# KinetisDIP.net
KiCad netlist of a schematic drawn in Altium Designer
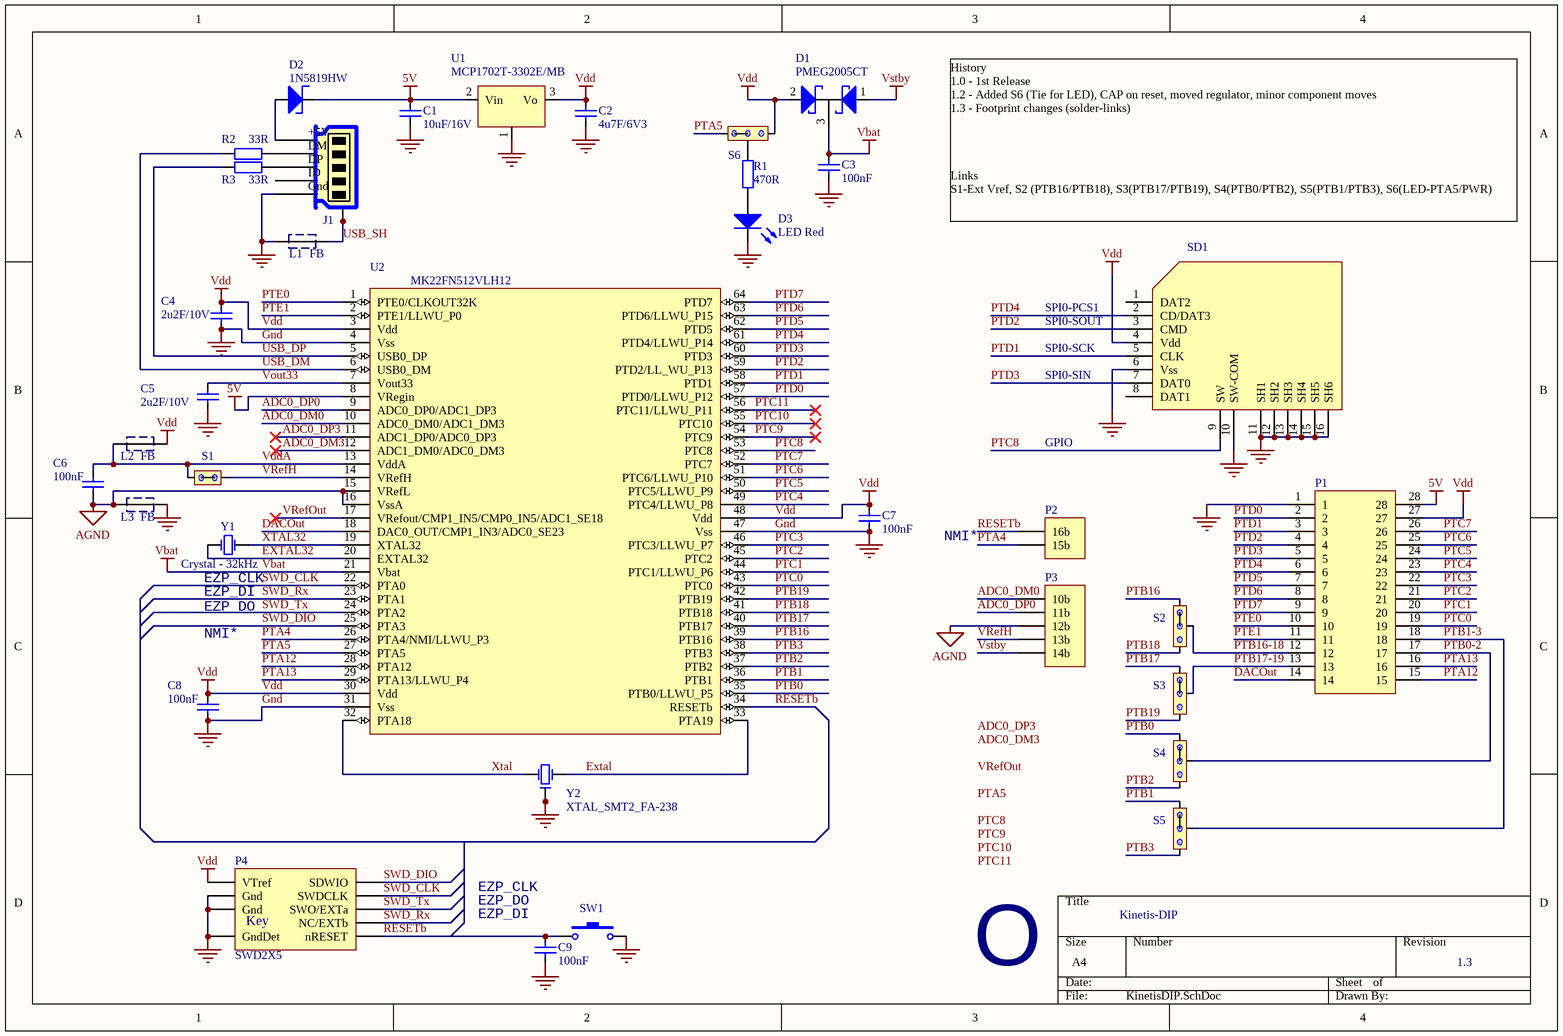
[diagram p0: KinetisDIP.SchDoc]

(export (version "E")
  (design (tool "Eeschema 10.0.6"))
  (components
    (comp (ref "C1")
      (value "10uF/16V")
      (footprint "CCNP2012-0805")
      (description "Capacitor SMT 0805")
      (fields
        (field (name "MANUFACTURER") "Generic Components")
        (field (name "PUBLISHER") "Altium Hobart Technology Centre")
      )
      (libsource (lib "MyLibrary") (part "Cap_CCNP_0805"))
    )
    (comp (ref "C2")
      (value "4u7F/6V3")
      (footprint "CCNP1608-0603")
      (description "Capacitor SMT 0603")
      (fields
        (field (name "MANUFACTURER") "Generic Components")
        (field (name "PUBLISHER") "Altium Hobart Technology Centre")
      )
      (libsource (lib "MyLibrary") (part "Cap_CCNP_0603"))
    )
    (comp (ref "C3")
      (value "100nF")
      (footprint "CCNP1608-0603")
      (description "Capacitor SMT 0603")
      (fields
        (field (name "MANUFACTURER") "Generic Components")
        (field (name "PUBLISHER") "Altium Hobart Technology Centre")
      )
      (libsource (lib "MyLibrary") (part "Cap_CCNP_0603"))
    )
    (comp (ref "C4")
      (value "2u2F/10V")
      (footprint "CCNP1608-0603")
      (description "Capacitor")
      (fields
        (field (name "MANUFACTURER") "Generic Components")
        (field (name "PUBLISHER") "Altium Hobart Technology Centre")
      )
      (libsource (lib "MyLibrary") (part "Cap"))
    )
    (comp (ref "C5")
      (value "2u2F/10V")
      (footprint "CCNP1608-0603")
      (description "Capacitor")
      (fields
        (field (name "MANUFACTURER") "Generic Components")
        (field (name "PUBLISHER") "Altium Hobart Technology Centre")
      )
      (libsource (lib "MyLibrary") (part "Cap"))
    )
    (comp (ref "C6")
      (value "100nF")
      (footprint "CCNP1608-0603")
      (description "Capacitor SMT 0603")
      (fields
        (field (name "MANUFACTURER") "Generic Components")
        (field (name "PUBLISHER") "Altium Hobart Technology Centre")
      )
      (libsource (lib "MyLibrary") (part "Cap_CCNP_0603"))
    )
    (comp (ref "C7")
      (value "100nF")
      (footprint "CCNP1608-0603")
      (description "Capacitor SMT 0603")
      (fields
        (field (name "MANUFACTURER") "Generic Components")
        (field (name "PUBLISHER") "Altium Hobart Technology Centre")
      )
      (libsource (lib "MyLibrary") (part "Cap_CCNP_0603"))
    )
    (comp (ref "C8")
      (value "100nF")
      (footprint "CCNP1608-0603")
      (description "Capacitor SMT 0603")
      (fields
        (field (name "MANUFACTURER") "Generic Components")
        (field (name "PUBLISHER") "Altium Hobart Technology Centre")
      )
      (libsource (lib "MyLibrary") (part "Cap_CCNP_0603"))
    )
    (comp (ref "C9")
      (value "100nF")
      (footprint "CCNP1608-0603")
      (description "Capacitor SMT 0603")
      (fields
        (field (name "MANUFACTURER") "Generic Components")
        (field (name "PUBLISHER") "Altium Hobart Technology Centre")
      )
      (libsource (lib "MyLibrary") (part "Cap_CCNP_0603"))
    )
    (comp (ref "D1")
      (value "PMEG2005CT")
      (footprint "SOT23")
      (description "Dual Schottky Diode (SMT)")
      (libsource (lib "MyLibrary") (part "PMEG2005CT"))
    )
    (comp (ref "D2")
      (value "1N5819HW")
      (footprint "SOD-123")
      (description "SCHOTTKY, 1A, 40V, SOD-123")
      (fields
        (field (name "MANUFACTURER") "Generic Components")
        (field (name "PUBLISHER") "Altium Hobart Technology Centre")
      )
      (libsource (lib "MySchLib") (part "1N5819HW"))
    )
    (comp (ref "D3")
      (value "LED Red")
      (footprint "LED1608-0603-RED")
      (description "LED 0603 Red")
      (fields (field (name "MANUFACTURER") "Generic Components") (field (name "PUBLISHER") "Altium Limited"))
      (libsource (lib "MyLibrary") (part "LED-0603-Red"))
    )
    (comp (ref "J1")
      (value "USB_MICRO_B_CONNECTOR")
      (footprint "MOLEX - 47346-0001")
      (description "USB Micro-B Connector")
      (libsource (lib "MySchLib") (part "USB_MICRO_B_CONNECTOR"))
    )
    (comp (ref "L1")
      (value "FB")
      (footprint "CR1608-0603")
      (description "Ferrite Bead (0603)")
      (libsource (lib "MyLibrary") (part "Ferrite Bead_0603"))
    )
    (comp (ref "L2")
      (value "FB")
      (footprint "CR1608-0603")
      (description "Ferrite Bead (0603)")
      (libsource (lib "MyLibrary") (part "Ferrite Bead_0603"))
    )
    (comp (ref "L3")
      (value "FB")
      (footprint "CR1608-0603")
      (description "Ferrite Bead (0603)")
      (libsource (lib "MyLibrary") (part "Ferrite Bead_0603"))
    )
    (comp (ref "Logo")
      (value "OSHW Logo")
      (footprint "OSHW")
      (libsource (lib "MyLibrary") (part "OSHW Logo"))
    )
    (comp (ref "P1")
      (value "WDIP-28-0.6")
      (footprint "WDIP-28-0.6")
      (description "Wide SIP package (0.6\")")
      (libsource (lib "MyLibrary") (part "WDIP-28-0.6"))
    )
    (comp (ref "P2")
      (value "Header 2")
      (footprint "HDR1X2")
      (description "Header, 2-Pin")
      (fields (field (name "PUBLISHER") "Altium Limited"))
      (libsource (lib "Miscellaneous Connectors") (part "Header 2"))
    )
    (comp (ref "P3")
      (value "Header 5")
      (footprint "HDR1X5")
      (description "Header, 5-Pin")
      (fields (field (name "PUBLISHER") "Altium Limited"))
      (libsource (lib "Miscellaneous Connectors") (part "Header 5"))
    )
    (comp (ref "P4")
      (value "SWD2X5")
      (footprint "SWD-2x5")
      (description "SWD Connector 2x5-Pin")
      (fields (field (name "PUBLISHER") "Altium Limited"))
      (libsource (lib "MySchLib") (part "SWD2X5"))
    )
    (comp (ref "R1")
      (value "470R")
      (footprint "CR1608-0603")
      (description "Resistor SMT")
      (fields
        (field (name "MANUFACTURER") "Generic Components")
        (field (name "PUBLISHER") "Altium Hobart Technology Centre")
      )
      (libsource (lib "MyLibrary") (part "Res"))
    )
    (comp (ref "R2")
      (value "33R")
      (footprint "CR1608-0603")
      (description "Resistor")
      (fields
        (field (name "MANUFACTURER") "Generic Components")
        (field (name "PUBLISHER") "Altium Hobart Technology Centre")
      )
      (libsource (lib "") (part "Res_1"))
    )
    (comp (ref "R3")
      (value "33R")
      (footprint "CR1608-0603")
      (description "Resistor")
      (fields
        (field (name "MANUFACTURER") "Generic Components")
        (field (name "PUBLISHER") "Altium Hobart Technology Centre")
      )
      (libsource (lib "") (part "Res_1"))
    )
    (comp (ref "S1")
      (value "LinkClosed")
      (footprint "SolderBridge(Closed)")
      (libsource (lib "MyLibrary") (part "LinkClosed"))
    )
    (comp (ref "S2")
      (value "Link3Closed")
      (footprint "SolderBridge3(Closed)")
      (libsource (lib "MySchLib") (part "Link3Closed"))
    )
    (comp (ref "S3")
      (value "Link3Closed")
      (footprint "SolderBridge3(Closed)")
      (libsource (lib "MySchLib") (part "Link3Closed"))
    )
    (comp (ref "S4")
      (value "Link3Closed")
      (footprint "SolderBridge3(Closed)")
      (libsource (lib "MySchLib") (part "Link3Closed"))
    )
    (comp (ref "S5")
      (value "Link3Closed")
      (footprint "SolderBridge3(Closed)")
      (libsource (lib "MySchLib") (part "Link3Closed"))
    )
    (comp (ref "S6")
      (value "Link3Closed")
      (footprint "SolderBridge3(Closed)")
      (libsource (lib "") (part "Link3Closed_1"))
    )
    (comp (ref "SD1")
      (value "SD_Socket2")
      (footprint "SDCARD_MICRO - MOLEX 504077-1891")
      (description "MOLEX  5040771891  CONNECTOR, MICRO SD, 1.1MM, 8 POSITION")
      (libsource (lib "MySchLib") (part "SD_Socket2"))
    )
    (comp (ref "SW1")
      (value "SW-PB-SMT-B3U")
      (footprint "SW_SMT_PB2-B3U")
      (description "Switch OMRON B3U series")
      (fields (field (name "MANUFACTURER") "Generic Components") (field (name "PUBLISHER") "Altium Limited"))
      (libsource (lib "MyLibrary") (part "SW-PB-SMT-B3U"))
    )
    (comp (ref "U1")
      (value "MCP1702T-3302E/MB")
      (footprint "SOT-89")
      (description "3V3 LDO regulator")
      (libsource (lib "MyLibrary") (part "MCP1702T-3302E/MB"))
    )
    (comp (ref "U2")
      (value "MK22FN512VLH12")
      (footprint "TSQFP50P1200X1200-64N")
      (description "Arm Cortex M4F")
      (libsource (lib "MySchLib") (part "MK22FN512VLH12"))
    )
    (comp (ref "Y1")
      (value "Crystal - 32kHz")
      (footprint "crystal_can")
      (description "CITIZEN CFS2016")
      (libsource (lib "MySchLib") (part "XTAL-32kHz_CITIZEN_CAN"))
    )
    (comp (ref "Y2")
      (value "XTAL_SMT2_FA-238")
      (footprint "Crystal_SMT - EPSON-FA-238")
      (description "Crystal (EPSON  Q22FA23800065 FA-238 24 MHZ 12.0PF)")
      (fields
        (field (name "MANUFACTURER") "Generic Components")
        (field (name "PUBLISHER") "Altium Hobart Technology Centre")
      )
      (libsource (lib "MyLibrary") (part "XTAL_SMT2_FA-238"))
    )
  )
  (nets
    (net (code "1") (name "/ADC0_DM0") (class "Default")
      (node (ref "P3") (pin "1") (pinfunction "10b_1") (pintype "passive"))
      (node (ref "U2") (pin "10") (pinfunction "ADC0_DM0/ADC1_DM3_10") (pintype "passive"))
    )
    (net (code "2") (name "/ADC0_DM3") (class "Default")
      (node (ref "U2") (pin "12") (pinfunction "ADC1_DM0/ADC0_DM3_12") (pintype "passive+no_connect"))
    )
    (net (code "3") (name "/ADC0_DP0") (class "Default")
      (node (ref "P3") (pin "2") (pinfunction "11b_2") (pintype "passive"))
      (node (ref "U2") (pin "9") (pinfunction "ADC0_DP0/ADC1_DP3_9") (pintype "passive"))
    )
    (net (code "4") (name "/ADC0_DP3") (class "Default")
      (node (ref "U2") (pin "11") (pinfunction "ADC1_DP0/ADC0_DP3_11") (pintype "passive+no_connect"))
    )
    (net (code "5") (name "/DACOut") (class "Default")
      (node (ref "P1") (pin "14") (pinfunction "14_14") (pintype "passive"))
      (node (ref "U2") (pin "18") (pinfunction "DAC0_OUT/CMP1_IN3/ADC0_SE23_18") (pintype "passive"))
    )
    (net (code "6") (name "/EXTAL32") (class "Default")
      (node (ref "U2") (pin "20") (pinfunction "EXTAL32_20") (pintype "passive"))
      (node (ref "Y1") (pin "2") (pinfunction "OSC2_2") (pintype "passive"))
    )
    (net (code "7") (name "/Extal") (class "Default")
      (node (ref "U2") (pin "33") (pinfunction "PTA19_33") (pintype "bidirectional"))
      (node (ref "Y2") (pin "3") (pinfunction "OSC2_3") (pintype "passive"))
    )
    (net (code "8") (name "/PTA4") (class "Default")
      (node (ref "P2") (pin "2") (pinfunction "15b_2") (pintype "passive"))
      (node (ref "U2") (pin "26") (pinfunction "PTA4/NMI/LLWU_P3_26") (pintype "bidirectional"))
    )
    (net (code "9") (name "/PTA5") (class "Default")
      (node (ref "S6") (pin "1") (pintype "passive"))
      (node (ref "U2") (pin "27") (pinfunction "PTA5_27") (pintype "bidirectional"))
    )
    (net (code "10") (name "/PTA12") (class "Default")
      (node (ref "P1") (pin "15") (pinfunction "15_15") (pintype "passive"))
      (node (ref "U2") (pin "28") (pinfunction "PTA12_28") (pintype "bidirectional"))
    )
    (net (code "11") (name "/PTA13") (class "Default")
      (node (ref "P1") (pin "16") (pinfunction "16_16") (pintype "passive"))
      (node (ref "U2") (pin "29") (pinfunction "PTA13/LLWU_P4_29") (pintype "bidirectional"))
    )
    (net (code "12") (name "/PTB0") (class "Default")
      (node (ref "S4") (pin "1") (pintype "passive"))
      (node (ref "U2") (pin "35") (pinfunction "PTB0/LLWU_P5_35") (pintype "bidirectional"))
    )
    (net (code "13") (name "/PTB0-2") (class "Default")
      (node (ref "P1") (pin "17") (pinfunction "17_17") (pintype "passive"))
      (node (ref "S4") (pin "2") (pintype "passive"))
    )
    (net (code "14") (name "/PTB1") (class "Default")
      (node (ref "S5") (pin "1") (pintype "passive"))
      (node (ref "U2") (pin "36") (pinfunction "PTB1_36") (pintype "bidirectional"))
    )
    (net (code "15") (name "/PTB1-3") (class "Default")
      (node (ref "P1") (pin "18") (pinfunction "18_18") (pintype "passive"))
      (node (ref "S5") (pin "2") (pintype "passive"))
    )
    (net (code "16") (name "/PTB2") (class "Default")
      (node (ref "S4") (pin "3") (pintype "passive"))
      (node (ref "U2") (pin "37") (pinfunction "PTB2_37") (pintype "bidirectional"))
    )
    (net (code "17") (name "/PTB3") (class "Default")
      (node (ref "S5") (pin "3") (pintype "passive"))
      (node (ref "U2") (pin "38") (pinfunction "PTB3_38") (pintype "bidirectional"))
    )
    (net (code "18") (name "/PTB16") (class "Default")
      (node (ref "S2") (pin "1") (pintype "passive"))
      (node (ref "U2") (pin "39") (pinfunction "PTB16_39") (pintype "bidirectional"))
    )
    (net (code "19") (name "/PTB16-18") (class "Default")
      (node (ref "P1") (pin "12") (pinfunction "12_12") (pintype "passive"))
      (node (ref "S2") (pin "2") (pintype "passive"))
    )
    (net (code "20") (name "/PTB17") (class "Default")
      (node (ref "S3") (pin "1") (pintype "passive"))
      (node (ref "U2") (pin "40") (pinfunction "PTB17_40") (pintype "bidirectional"))
    )
    (net (code "21") (name "/PTB17-19") (class "Default")
      (node (ref "P1") (pin "13") (pinfunction "13_13") (pintype "passive"))
      (node (ref "S3") (pin "2") (pintype "passive"))
    )
    (net (code "22") (name "/PTB18") (class "Default")
      (node (ref "S2") (pin "3") (pintype "passive"))
      (node (ref "U2") (pin "41") (pinfunction "PTB18_41") (pintype "bidirectional"))
    )
    (net (code "23") (name "/PTB19") (class "Default")
      (node (ref "S3") (pin "3") (pintype "passive"))
      (node (ref "U2") (pin "42") (pinfunction "PTB19_42") (pintype "bidirectional"))
    )
    (net (code "24") (name "/PTC0") (class "Default")
      (node (ref "P1") (pin "19") (pinfunction "19_19") (pintype "passive"))
      (node (ref "U2") (pin "43") (pinfunction "PTC0_43") (pintype "bidirectional"))
    )
    (net (code "25") (name "/PTC1") (class "Default")
      (node (ref "P1") (pin "20") (pinfunction "20_20") (pintype "passive"))
      (node (ref "U2") (pin "44") (pinfunction "PTC1/LLWU_P6_44") (pintype "bidirectional"))
    )
    (net (code "26") (name "/PTC2") (class "Default")
      (node (ref "P1") (pin "21") (pinfunction "21_21") (pintype "passive"))
      (node (ref "U2") (pin "45") (pinfunction "PTC2_45") (pintype "bidirectional"))
    )
    (net (code "27") (name "/PTC3") (class "Default")
      (node (ref "P1") (pin "22") (pinfunction "22_22") (pintype "passive"))
      (node (ref "U2") (pin "46") (pinfunction "PTC3/LLWU_P7_46") (pintype "bidirectional"))
    )
    (net (code "28") (name "/PTC4") (class "Default")
      (node (ref "P1") (pin "23") (pinfunction "23_23") (pintype "passive"))
      (node (ref "U2") (pin "49") (pinfunction "PTC4/LLWU_P8_49") (pintype "power_in"))
    )
    (net (code "29") (name "/PTC5") (class "Default")
      (node (ref "P1") (pin "24") (pinfunction "24_24") (pintype "passive"))
      (node (ref "U2") (pin "50") (pinfunction "PTC5/LLWU_P9_50") (pintype "bidirectional"))
    )
    (net (code "30") (name "/PTC6") (class "Default")
      (node (ref "P1") (pin "25") (pinfunction "25_25") (pintype "passive"))
      (node (ref "U2") (pin "51") (pinfunction "PTC6/LLWU_P10_51") (pintype "bidirectional"))
    )
    (net (code "31") (name "/PTC7") (class "Default")
      (node (ref "P1") (pin "26") (pinfunction "26_26") (pintype "passive"))
      (node (ref "U2") (pin "52") (pinfunction "PTC7_52") (pintype "bidirectional"))
    )
    (net (code "32") (name "/PTC8") (class "Default")
      (node (ref "SD1") (pin "9") (pinfunction "SW_9") (pintype "passive"))
      (node (ref "U2") (pin "53") (pinfunction "PTC8_53") (pintype "bidirectional"))
    )
    (net (code "33") (name "/PTC9") (class "Default")
      (node (ref "U2") (pin "54") (pinfunction "PTC9_54") (pintype "bidirectional+no_connect"))
    )
    (net (code "34") (name "/PTC10") (class "Default")
      (node (ref "U2") (pin "55") (pinfunction "PTC10_55") (pintype "bidirectional+no_connect"))
    )
    (net (code "35") (name "/PTC11") (class "Default")
      (node (ref "U2") (pin "56") (pinfunction "PTC11/LLWU_P11_56") (pintype "bidirectional+no_connect"))
    )
    (net (code "36") (name "/PTD0") (class "Default")
      (node (ref "P1") (pin "2") (pinfunction "2_2") (pintype "passive"))
      (node (ref "U2") (pin "57") (pinfunction "PTD0/LLWU_P12_57") (pintype "bidirectional"))
    )
    (net (code "37") (name "/PTD1") (class "Default")
      (node (ref "P1") (pin "3") (pinfunction "3_3") (pintype "passive"))
      (node (ref "SD1") (pin "5") (pinfunction "CLK_5") (pintype "passive"))
      (node (ref "U2") (pin "58") (pinfunction "PTD1_58") (pintype "bidirectional"))
    )
    (net (code "38") (name "/PTD2") (class "Default")
      (node (ref "P1") (pin "4") (pinfunction "4_4") (pintype "passive"))
      (node (ref "SD1") (pin "3") (pinfunction "CMD_3") (pintype "passive"))
      (node (ref "U2") (pin "59") (pinfunction "PTD2/LL_WU_P13_59") (pintype "bidirectional"))
    )
    (net (code "39") (name "/PTD3") (class "Default")
      (node (ref "P1") (pin "5") (pinfunction "5_5") (pintype "passive"))
      (node (ref "SD1") (pin "7") (pinfunction "DAT0_7") (pintype "passive"))
      (node (ref "U2") (pin "60") (pinfunction "PTD3_60") (pintype "bidirectional"))
    )
    (net (code "40") (name "/PTD4") (class "Default")
      (node (ref "P1") (pin "6") (pinfunction "6_6") (pintype "passive"))
      (node (ref "SD1") (pin "2") (pinfunction "CD/DAT3_2") (pintype "passive"))
      (node (ref "U2") (pin "61") (pinfunction "PTD4/LLWU_P14_61") (pintype "bidirectional"))
    )
    (net (code "41") (name "/PTD5") (class "Default")
      (node (ref "P1") (pin "7") (pinfunction "7_7") (pintype "passive"))
      (node (ref "U2") (pin "62") (pinfunction "PTD5_62") (pintype "bidirectional"))
    )
    (net (code "42") (name "/PTD6") (class "Default")
      (node (ref "P1") (pin "8") (pinfunction "8_8") (pintype "passive"))
      (node (ref "U2") (pin "63") (pinfunction "PTD6/LLWU_P15_63") (pintype "bidirectional"))
    )
    (net (code "43") (name "/PTD7") (class "Default")
      (node (ref "P1") (pin "9") (pinfunction "9_9") (pintype "passive"))
      (node (ref "U2") (pin "64") (pinfunction "PTD7_64") (pintype "bidirectional"))
    )
    (net (code "44") (name "/PTE0") (class "Default")
      (node (ref "P1") (pin "10") (pinfunction "10_10") (pintype "passive"))
      (node (ref "U2") (pin "1") (pinfunction "PTE0/CLKOUT32K_1") (pintype "bidirectional"))
    )
    (net (code "45") (name "/PTE1") (class "Default")
      (node (ref "P1") (pin "11") (pinfunction "11_11") (pintype "passive"))
      (node (ref "U2") (pin "2") (pinfunction "PTE1/LLWU_P0_2") (pintype "bidirectional"))
    )
    (net (code "46") (name "/RESETb") (class "Default")
      (node (ref "C9") (pin "1") (pinfunction "1_1") (pintype "passive"))
      (node (ref "P2") (pin "1") (pinfunction "16b_1") (pintype "passive"))
      (node (ref "P4") (pin "10") (pinfunction "nRESET_10") (pintype "passive"))
      (node (ref "SW1") (pin "1") (pinfunction "1_1") (pintype "passive"))
      (node (ref "U2") (pin "34") (pinfunction "RESETb_34") (pintype "bidirectional"))
    )
    (net (code "47") (name "/SWD_CLK") (class "Default")
      (node (ref "P4") (pin "4") (pinfunction "SWDCLK_4") (pintype "passive"))
      (node (ref "U2") (pin "22") (pinfunction "PTA0_22") (pintype "bidirectional"))
    )
    (net (code "48") (name "/SWD_DIO") (class "Default")
      (node (ref "P4") (pin "2") (pinfunction "SDWIO_2") (pintype "passive"))
      (node (ref "U2") (pin "25") (pinfunction "PTA3_25") (pintype "bidirectional"))
    )
    (net (code "49") (name "/SWD_Rx") (class "Default")
      (node (ref "P4") (pin "8") (pinfunction "NC/EXTb_8") (pintype "passive"))
      (node (ref "U2") (pin "23") (pinfunction "PTA1_23") (pintype "bidirectional"))
    )
    (net (code "50") (name "/SWD_Tx") (class "Default")
      (node (ref "P4") (pin "6") (pinfunction "SWO/EXTa_6") (pintype "passive"))
      (node (ref "U2") (pin "24") (pinfunction "PTA2_24") (pintype "bidirectional"))
    )
    (net (code "51") (name "/USB_DM") (class "Default")
      (node (ref "R2") (pin "2") (pinfunction "2_2") (pintype "passive"))
      (node (ref "U2") (pin "6") (pinfunction "USB0_DM_6") (pintype "bidirectional"))
    )
    (net (code "52") (name "/USB_DP") (class "Default")
      (node (ref "R3") (pin "2") (pinfunction "2_2") (pintype "passive"))
      (node (ref "U2") (pin "5") (pinfunction "USB0_DP_5") (pintype "bidirectional"))
    )
    (net (code "53") (name "/USB_SH") (class "Default")
      (node (ref "J1") (pin "S1") (pinfunction "USBShd_S1") (pintype "passive"))
      (node (ref "J1") (pin "S2") (pinfunction "USBShd_S2") (pintype "passive"))
      (node (ref "J1") (pin "S3") (pinfunction "USBShd_S3") (pintype "passive"))
      (node (ref "J1") (pin "S4") (pinfunction "USBShd_S4") (pintype "passive"))
      (node (ref "J1") (pin "S5") (pinfunction "USBShd_S5") (pintype "passive"))
      (node (ref "J1") (pin "S6") (pinfunction "USBShd_S6") (pintype "passive"))
      (node (ref "L1") (pin "2") (pinfunction "2_2") (pintype "passive"))
    )
    (net (code "54") (name "/VRefH") (class "Default")
      (node (ref "P3") (pin "4") (pinfunction "13b_4") (pintype "passive"))
      (node (ref "S1") (pin "2") (pintype "passive"))
      (node (ref "U2") (pin "14") (pinfunction "VRefH_14") (pintype "passive"))
    )
    (net (code "55") (name "/VRefOut") (class "Default")
      (node (ref "U2") (pin "17") (pinfunction "VRefout/CMP1_IN5/CMP0_IN5/ADC1_SE18_17") (pintype "passive+no_connect"))
    )
    (net (code "56") (name "/VddA") (class "Default")
      (node (ref "C6") (pin "1") (pinfunction "1_1") (pintype "passive"))
      (node (ref "L2") (pin "2") (pinfunction "2_2") (pintype "passive"))
      (node (ref "S1") (pin "1") (pintype "passive"))
      (node (ref "U2") (pin "13") (pinfunction "VddA_13") (pintype "power_in"))
    )
    (net (code "57") (name "/Vout33") (class "Default")
      (node (ref "C5") (pin "2") (pinfunction "2_2") (pintype "passive"))
      (node (ref "U2") (pin "7") (pinfunction "Vout33_7") (pintype "power_in"))
    )
    (net (code "58") (name "/XTAL32") (class "Default")
      (node (ref "U2") (pin "19") (pinfunction "XTAL32_19") (pintype "passive"))
      (node (ref "Y1") (pin "1") (pinfunction "OSC1_1") (pintype "passive"))
    )
    (net (code "59") (name "/Xtal") (class "Default")
      (node (ref "U2") (pin "32") (pinfunction "PTA18_32") (pintype "bidirectional"))
      (node (ref "Y2") (pin "1") (pinfunction "OSC1_1") (pintype "passive"))
    )
    (net (code "60") (name "5V") (class "Default")
      (node (ref "C1") (pin "2") (pinfunction "2_2") (pintype "passive"))
      (node (ref "D2") (pin "2") (pinfunction "K_2") (pintype "passive"))
      (node (ref "P1") (pin "28") (pinfunction "28_28") (pintype "passive"))
      (node (ref "U1") (pin "2") (pinfunction "Vin_2") (pintype "passive"))
      (node (ref "U2") (pin "8") (pinfunction "VRegin_8") (pintype "passive"))
    )
    (net (code "61") (name "AGND") (class "Default")
      (node (ref "C6") (pin "2") (pinfunction "2_2") (pintype "passive"))
      (node (ref "L3") (pin "2") (pinfunction "2_2") (pintype "passive"))
      (node (ref "P3") (pin "3") (pinfunction "12b_3") (pintype "passive"))
      (node (ref "U2") (pin "15") (pinfunction "VRefL_15") (pintype "passive"))
      (node (ref "U2") (pin "16") (pinfunction "VssA_16") (pintype "power_in"))
    )
    (net (code "62") (name "GND") (class "Default")
      (node (ref "C1") (pin "1") (pinfunction "1_1") (pintype "passive"))
      (node (ref "C2") (pin "2") (pinfunction "2_2") (pintype "passive"))
      (node (ref "C3") (pin "2") (pinfunction "2_2") (pintype "passive"))
      (node (ref "C4") (pin "1") (pinfunction "1_1") (pintype "passive"))
      (node (ref "C5") (pin "1") (pinfunction "1_1") (pintype "passive"))
      (node (ref "C7") (pin "2") (pinfunction "2_2") (pintype "passive"))
      (node (ref "C8") (pin "2") (pinfunction "2_2") (pintype "passive"))
      (node (ref "C9") (pin "2") (pinfunction "2_2") (pintype "passive"))
      (node (ref "D3") (pin "K") (pinfunction "K_K") (pintype "passive"))
      (node (ref "J1") (pin "G") (pinfunction "USBGnd_G") (pintype "passive"))
      (node (ref "L1") (pin "1") (pinfunction "1_1") (pintype "passive"))
      (node (ref "L3") (pin "1") (pinfunction "1_1") (pintype "passive"))
      (node (ref "P1") (pin "1") (pinfunction "1_1") (pintype "passive"))
      (node (ref "P4") (pin "3") (pinfunction "Gnd_3") (pintype "passive"))
      (node (ref "P4") (pin "5") (pinfunction "Gnd_5") (pintype "passive"))
      (node (ref "P4") (pin "9") (pinfunction "GndDet_9") (pintype "passive"))
      (node (ref "SD1") (pin "10") (pinfunction "SW-COM_10") (pintype "passive"))
      (node (ref "SD1") (pin "11") (pinfunction "SH1_11") (pintype "passive"))
      (node (ref "SD1") (pin "12") (pinfunction "SH2_12") (pintype "passive"))
      (node (ref "SD1") (pin "13") (pinfunction "SH3_13") (pintype "passive"))
      (node (ref "SD1") (pin "14") (pinfunction "SH4_14") (pintype "passive"))
      (node (ref "SD1") (pin "15") (pinfunction "SH5_15") (pintype "passive"))
      (node (ref "SD1") (pin "16") (pinfunction "SH6_16") (pintype "passive"))
      (node (ref "SD1") (pin "6") (pinfunction "Vss_6") (pintype "passive"))
      (node (ref "SW1") (pin "2") (pinfunction "2_2") (pintype "passive"))
      (node (ref "U1") (pin "1") (pinfunction "Gnd_1") (pintype "passive"))
      (node (ref "U2") (pin "31") (pinfunction "Vss_31") (pintype "power_in"))
      (node (ref "U2") (pin "4") (pinfunction "Vss_4") (pintype "power_in"))
      (node (ref "U2") (pin "47") (pinfunction "Vss_47") (pintype "power_in"))
      (node (ref "Y2") (pin "2") (pinfunction "Gnd_2") (pintype "passive"))
      (node (ref "Y2") (pin "4") (pinfunction "Gnd_4") (pintype "passive"))
    )
    (net (code "63") (name "Net-(D2-A)") (class "Default")
      (node (ref "D2") (pin "1") (pinfunction "A_1") (pintype "passive"))
      (node (ref "J1") (pin "VBUS") (pinfunction "USB+5v_VBUS") (pintype "power_in"))
    )
    (net (code "64") (name "Net-(D3-PadA)") (class "Default")
      (node (ref "D3") (pin "A") (pinfunction "A_A") (pintype "passive"))
      (node (ref "R1") (pin "1") (pinfunction "1_1") (pintype "passive"))
    )
    (net (code "65") (name "Net-(J1-USBDM)") (class "Default")
      (node (ref "J1") (pin "D-") (pinfunction "USBDM_D-") (pintype "passive"))
      (node (ref "R2") (pin "1") (pinfunction "1_1") (pintype "passive"))
    )
    (net (code "66") (name "Net-(J1-USBDP)") (class "Default")
      (node (ref "J1") (pin "D+") (pinfunction "USBDP_D+") (pintype "passive"))
      (node (ref "R3") (pin "1") (pinfunction "1_1") (pintype "passive"))
    )
    (net (code "67") (name "Net-(R1-Pad2)") (class "Default")
      (node (ref "R1") (pin "2") (pinfunction "2_2") (pintype "passive"))
      (node (ref "S6") (pin "2") (pintype "passive"))
    )
    (net (code "68") (name "Vbat") (class "Default")
      (node (ref "C3") (pin "1") (pinfunction "1_1") (pintype "passive"))
      (node (ref "D1") (pin "3") (pinfunction "K_3") (pintype "passive"))
      (node (ref "U2") (pin "21") (pinfunction "Vbat_21") (pintype "passive"))
    )
    (net (code "69") (name "Vdd") (class "Default")
      (node (ref "C2") (pin "1") (pinfunction "1_1") (pintype "passive"))
      (node (ref "C4") (pin "2") (pinfunction "2_2") (pintype "passive"))
      (node (ref "C7") (pin "1") (pinfunction "1_1") (pintype "passive"))
      (node (ref "C8") (pin "1") (pinfunction "1_1") (pintype "passive"))
      (node (ref "D1") (pin "2") (pinfunction "A2_2") (pintype "passive"))
      (node (ref "L2") (pin "1") (pinfunction "1_1") (pintype "passive"))
      (node (ref "P1") (pin "27") (pinfunction "27_27") (pintype "passive"))
      (node (ref "P4") (pin "1") (pinfunction "VTref_1") (pintype "passive"))
      (node (ref "S6") (pin "3") (pintype "passive"))
      (node (ref "SD1") (pin "4") (pinfunction "Vdd_4") (pintype "passive"))
      (node (ref "U1") (pin "3") (pinfunction "Vo_3") (pintype "passive"))
      (node (ref "U2") (pin "3") (pinfunction "Vdd_3") (pintype "power_in"))
      (node (ref "U2") (pin "30") (pinfunction "Vdd_30") (pintype "power_in"))
      (node (ref "U2") (pin "48") (pinfunction "Vdd_48") (pintype "power_in"))
    )
    (net (code "70") (name "Vstby") (class "Default")
      (node (ref "D1") (pin "1") (pinfunction "A1_1") (pintype "passive"))
      (node (ref "P3") (pin "5") (pinfunction "14b_5") (pintype "passive"))
    )
    (net (code "71") (name "unconnected-(J1-USB_ID-PadID)") (class "Default")
      (node (ref "J1") (pin "ID") (pinfunction "USB_ID_ID") (pintype "passive"))
    )
    (net (code "72") (name "unconnected-(SD1-DAT1-Pad8)") (class "Default")
      (node (ref "SD1") (pin "8") (pinfunction "DAT1_8") (pintype "passive"))
    )
    (net (code "73") (name "unconnected-(SD1-DAT2-Pad1)") (class "Default")
      (node (ref "SD1") (pin "1") (pinfunction "DAT2_1") (pintype "passive"))
    )
  )
)
